# AKU350-Silicon-Mic_Rev-A.net
KiCad netlist of a schematic drawn in EAGLE
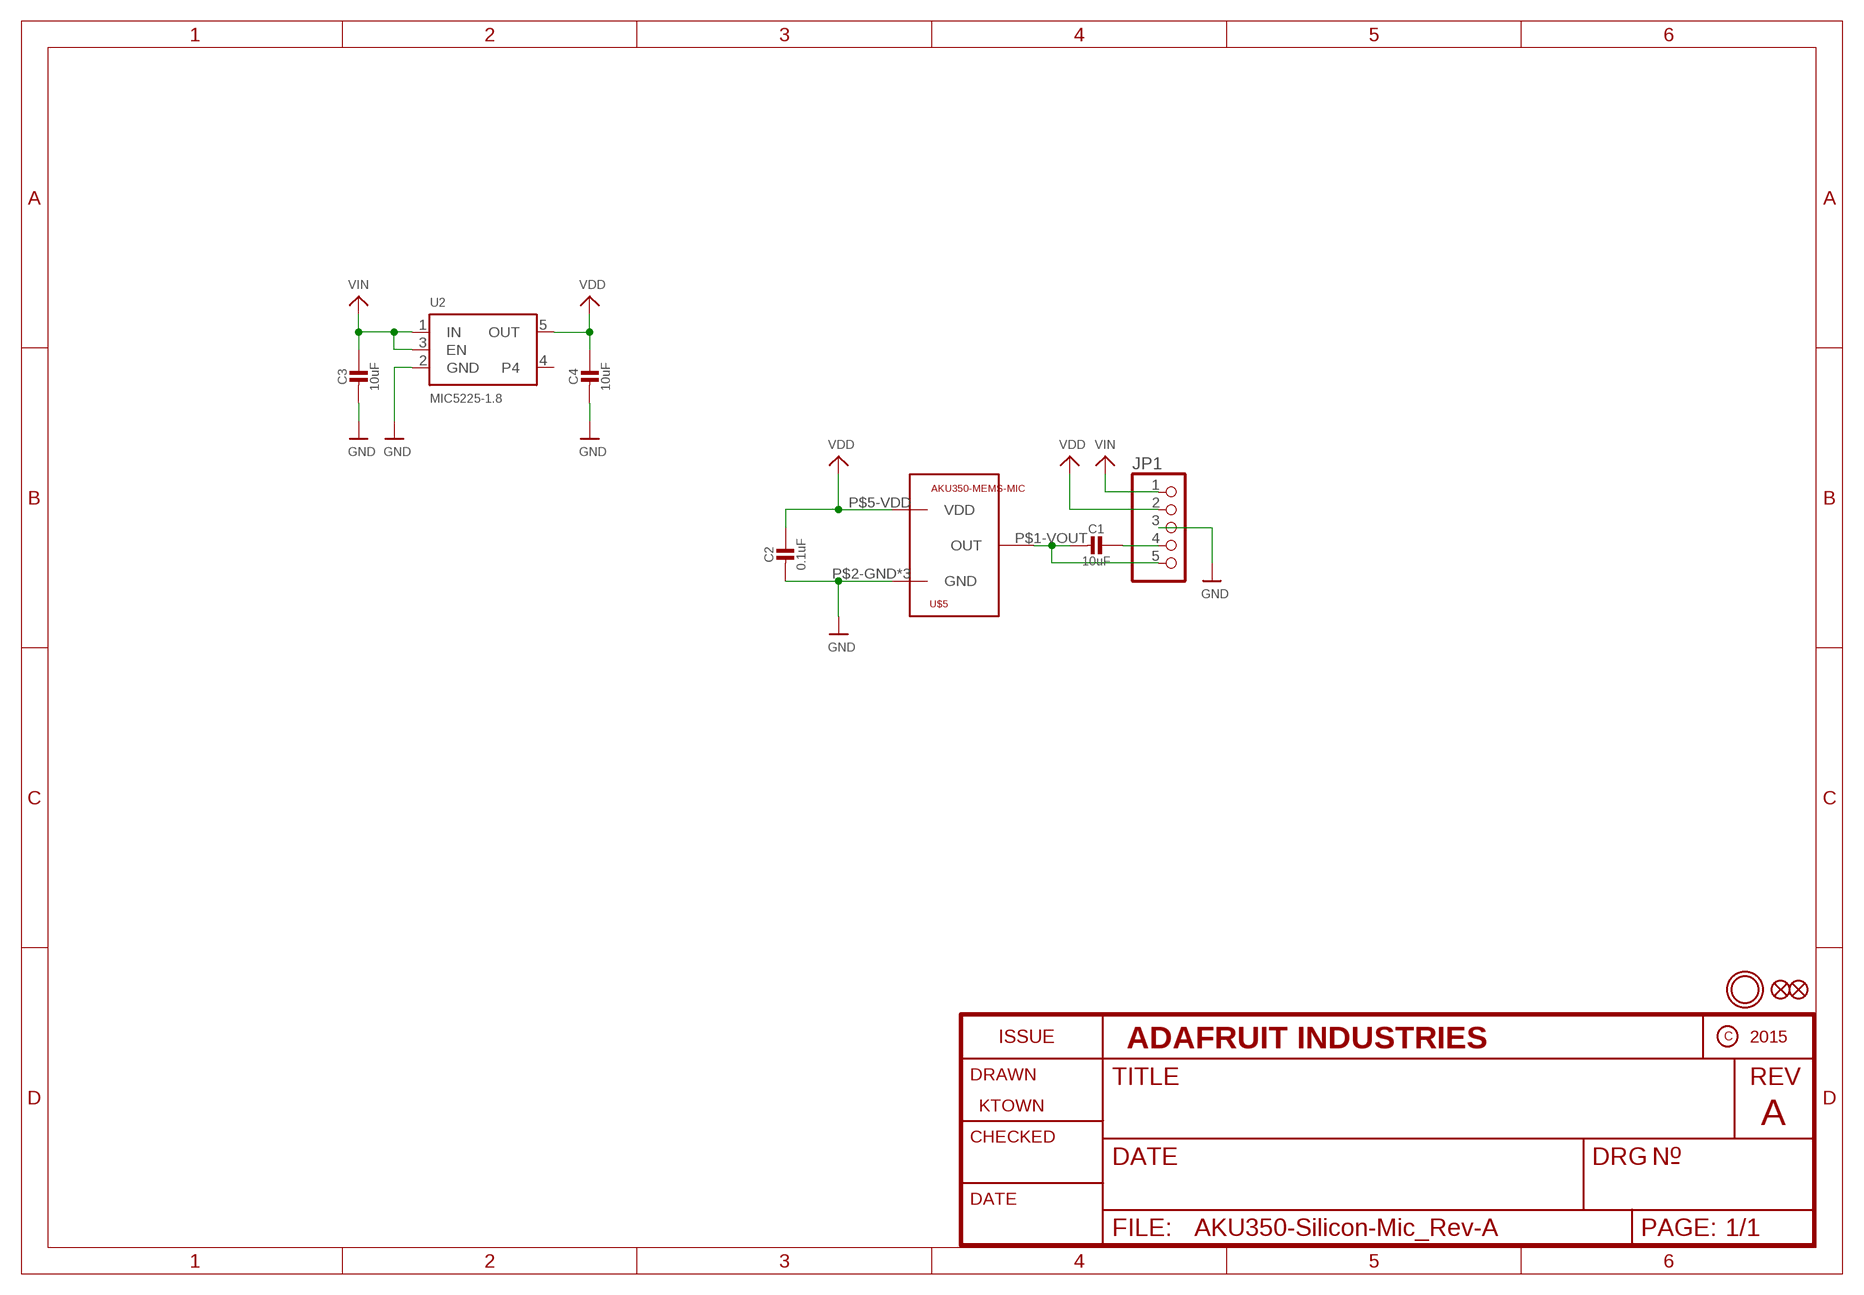
[diagram p0: schematic, sheet 1]

(export (version "E")
  (design (tool "Eeschema 10.0.6"))
  (components
    (comp (ref "C1")
      (value "10uF")
      (footprint "eagle-import:0805-NO")
      (libsource (lib "eagle-import") (part "CAP_CERAMIC0805-NOOUTLINE"))
    )
    (comp (ref "C2")
      (value "0.1uF")
      (footprint "eagle-import:0805-NO")
      (libsource (lib "eagle-import") (part "CAP_CERAMIC0805-NOOUTLINE"))
    )
    (comp (ref "C3")
      (value "10uF")
      (footprint "eagle-import:0805-NO")
      (libsource (lib "eagle-import") (part "CAP_CERAMIC0805-NOOUTLINE"))
    )
    (comp (ref "C4")
      (value "10uF")
      (footprint "eagle-import:0805-NO")
      (libsource (lib "eagle-import") (part "CAP_CERAMIC0805-NOOUTLINE"))
    )
    (comp (ref "FID1")
      (value "FIDUCIAL\"\"")
      (footprint "eagle-import:FIDUCIAL_1MM")
      (libsource (lib "eagle-import") (part "FIDUCIAL{dblquote}{dblquote}"))
    )
    (comp (ref "FID2")
      (value "FIDUCIAL\"\"")
      (footprint "eagle-import:FIDUCIAL_1MM")
      (libsource (lib "eagle-import") (part "FIDUCIAL{dblquote}{dblquote}"))
    )
    (comp (ref "JP1")
      (value "HEADER-1X576MIL")
      (footprint "eagle-import:1X05_ROUND_76")
      (libsource (lib "eagle-import") (part "HEADER-1X576MIL"))
    )
    (comp (ref "U$5")
      (value "AKU350-MEMS-MIC")
      (footprint "eagle-import:AKU350-MEMS-MIC")
      (libsource (lib "eagle-import") (part "AKU350-MEMS-MIC"))
    )
    (comp (ref "U$12")
      (value "MOUNTINGHOLE2.5")
      (footprint "eagle-import:MOUNTINGHOLE_2.5_PLATED")
      (libsource (lib "eagle-import") (part "MOUNTINGHOLE2.5"))
    )
    (comp (ref "U2")
      (value "MIC5225-1.8")
      (footprint "eagle-import:SOT23-5")
      (libsource (lib "eagle-import") (part "VREG_SOT23-5"))
    )
  )
  (nets
    (net (code "1") (name "GND") (class "Default")
      (node (ref "C2") (pin "2") (pinfunction "2_2") (pintype "passive"))
      (node (ref "C3") (pin "2") (pinfunction "2_2") (pintype "passive"))
      (node (ref "C4") (pin "2") (pinfunction "2_2") (pintype "passive"))
      (node (ref "JP1") (pin "3") (pinfunction "3_3") (pintype "passive"))
      (node (ref "U$5") (pin "P$2-GND") (pinfunction "GND_P$2-GND") (pintype "bidirectional"))
      (node (ref "U$5") (pin "P$3-GND") (pinfunction "GND_P$3-GND") (pintype "bidirectional"))
      (node (ref "U$5") (pin "P$4-GND") (pinfunction "GND_P$4-GND") (pintype "bidirectional"))
      (node (ref "U2") (pin "2") (pinfunction "GND_2") (pintype "power_in"))
    )
    (net (code "2") (name "Net-(C1-Pad1)") (class "Default")
      (node (ref "C1") (pin "1") (pinfunction "1_1") (pintype "passive"))
      (node (ref "JP1") (pin "4") (pinfunction "4_4") (pintype "passive"))
    )
    (net (code "3") (name "Net-(U$5-OUT)") (class "Default")
      (node (ref "C1") (pin "2") (pinfunction "2_2") (pintype "passive"))
      (node (ref "JP1") (pin "5") (pinfunction "5_5") (pintype "passive"))
      (node (ref "U$5") (pin "P$1-VOUT") (pinfunction "OUT_P$1-VOUT") (pintype "bidirectional"))
    )
    (net (code "4") (name "VDD") (class "Default")
      (node (ref "C2") (pin "1") (pinfunction "1_1") (pintype "passive"))
      (node (ref "C4") (pin "1") (pinfunction "1_1") (pintype "passive"))
      (node (ref "JP1") (pin "2") (pinfunction "2_2") (pintype "passive"))
      (node (ref "U$5") (pin "P$5-VDD") (pinfunction "VDD_P$5-VDD") (pintype "bidirectional"))
      (node (ref "U2") (pin "5") (pinfunction "OUT_5") (pintype "power_in"))
    )
    (net (code "5") (name "VIN") (class "Default")
      (node (ref "C3") (pin "1") (pinfunction "1_1") (pintype "passive"))
      (node (ref "JP1") (pin "1") (pinfunction "1_1") (pintype "passive"))
      (node (ref "U2") (pin "1") (pinfunction "IN_1") (pintype "power_in"))
      (node (ref "U2") (pin "3") (pinfunction "EN_3") (pintype "input"))
    )
    (net (code "6") (name "unconnected-(U2-P4-Pad4)") (class "Default")
      (node (ref "U2") (pin "4") (pinfunction "P4_4") (pintype "bidirectional"))
    )
  )
)
